# Audio_Amplifier.net
KiCad netlist of a schematic drawn in EAGLE
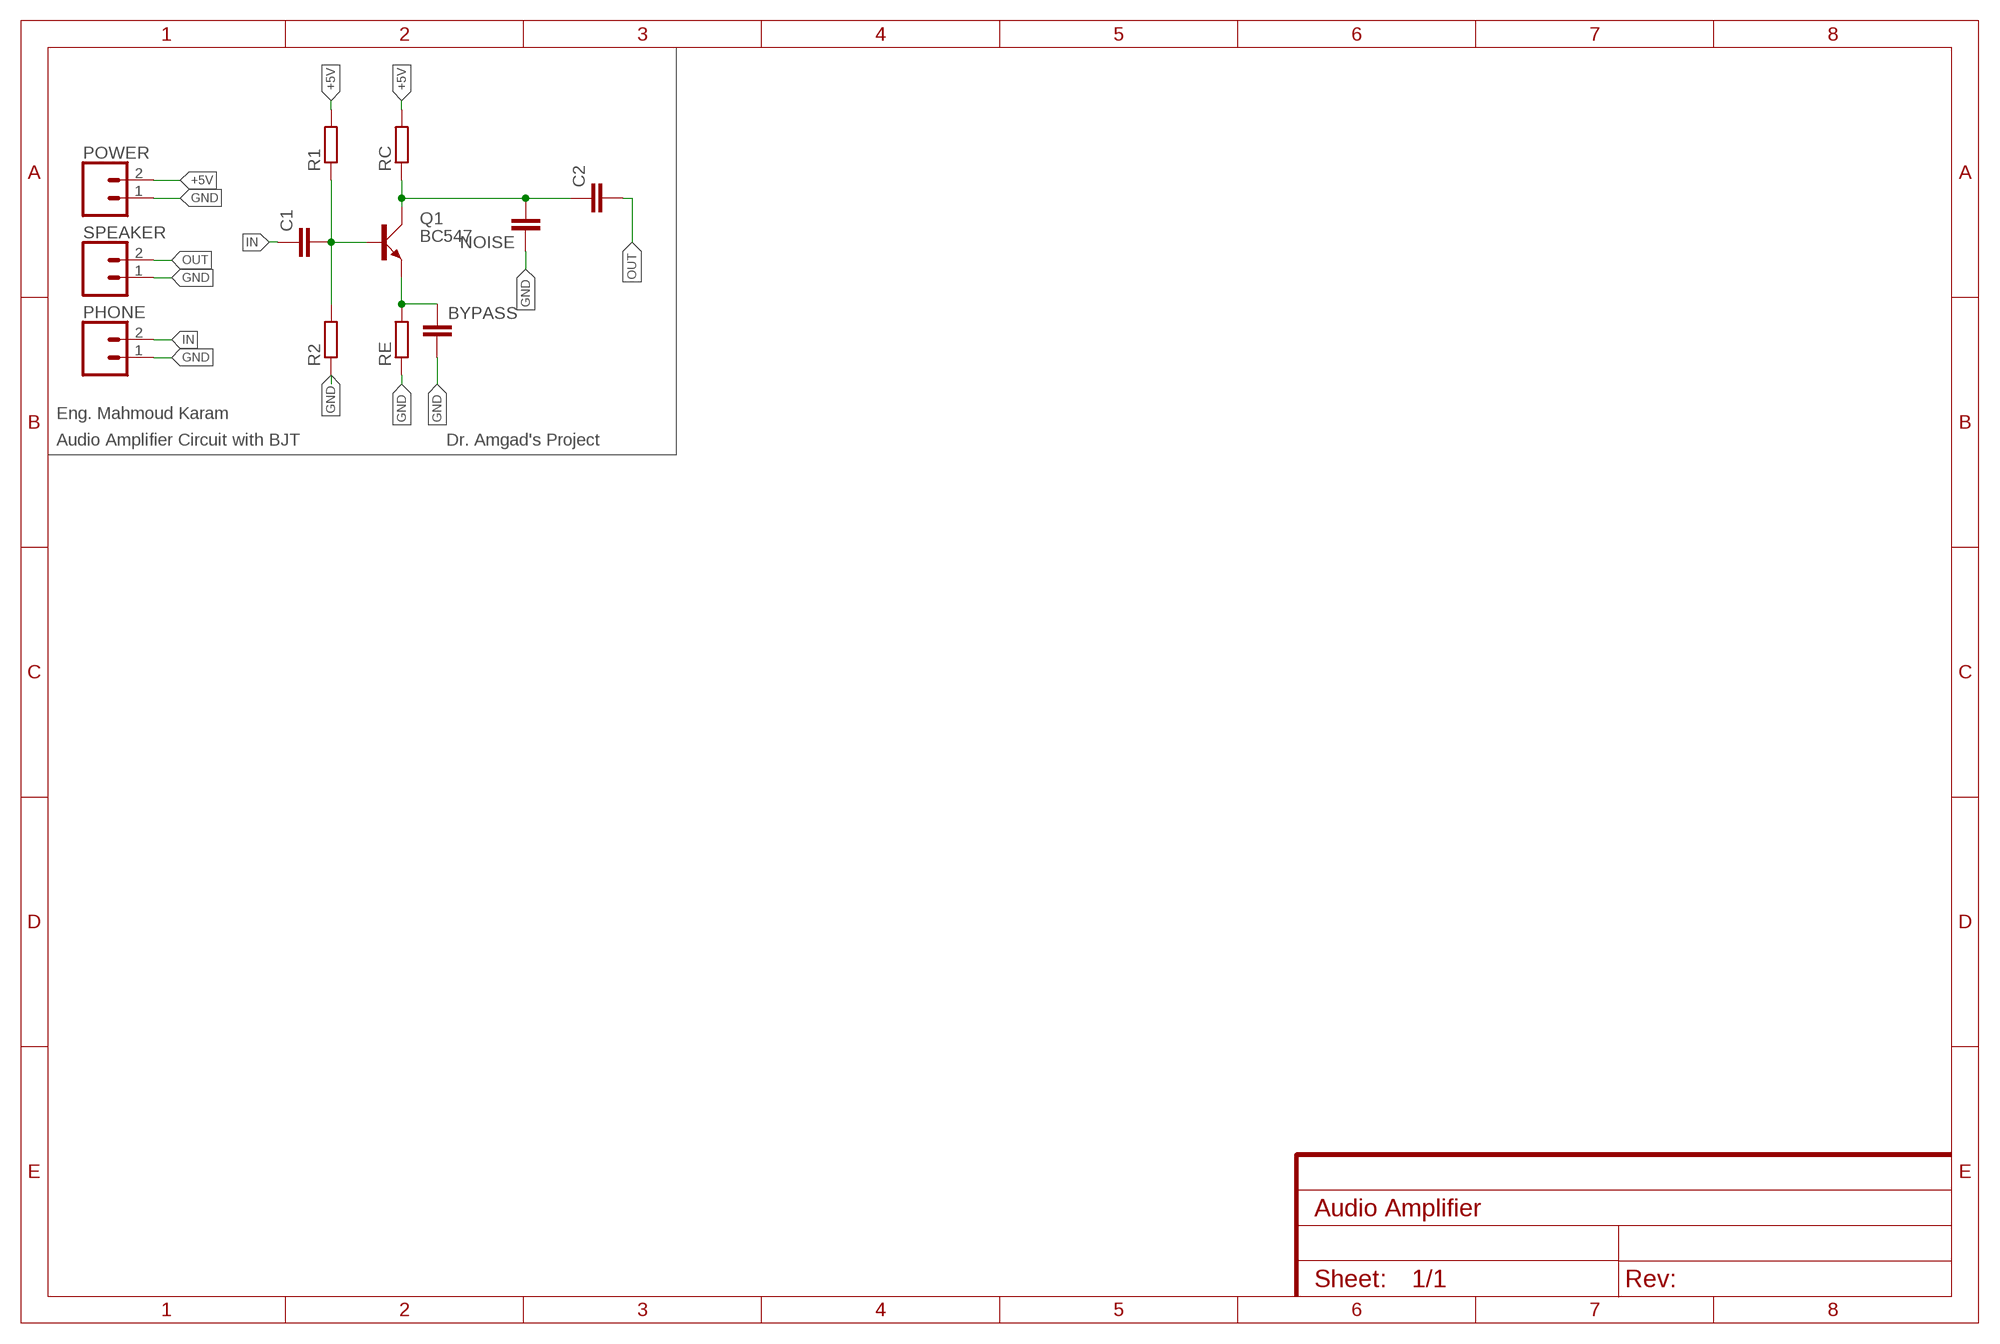
[diagram p0: schematic, sheet 1]

(export (version "E")
  (design (tool "Eeschema 10.0.6"))
  (components
    (comp (ref "BYPASS")
      (value "C10/4")
      (footprint "eagle-import:C10B4")
      (libsource (lib "eagle-import") (part "C10/4"))
    )
    (comp (ref "C1")
      (value "C2.5/5")
      (footprint "eagle-import:C2.5-5")
      (libsource (lib "eagle-import") (part "C2.5/5"))
    )
    (comp (ref "C2")
      (value "C2.5/5")
      (footprint "eagle-import:C2.5-5")
      (libsource (lib "eagle-import") (part "C2.5/5"))
    )
    (comp (ref "NOISE")
      (value "C2.5/5")
      (footprint "eagle-import:C2.5-5")
      (libsource (lib "eagle-import") (part "C2.5/5"))
    )
    (comp (ref "PHONE")
      (value "CONN_02JST-PTH-2")
      (footprint "eagle-import:JST-2-PTH")
      (libsource (lib "eagle-import") (part "CONN_02JST-PTH-2"))
    )
    (comp (ref "POWER")
      (value "CONN_02JST-PTH-2")
      (footprint "eagle-import:JST-2-PTH")
      (libsource (lib "eagle-import") (part "CONN_02JST-PTH-2"))
    )
    (comp (ref "Q1")
      (value "BC547")
      (footprint "eagle-import:SOT54A")
      (libsource (lib "eagle-import") (part "BC547"))
    )
    (comp (ref "R1")
      (value "R-EU_0204/7")
      (footprint "eagle-import:0204_7")
      (libsource (lib "eagle-import") (part "R-EU_0204/7"))
    )
    (comp (ref "R2")
      (value "R-EU_0204/7")
      (footprint "eagle-import:0204_7")
      (libsource (lib "eagle-import") (part "R-EU_0204/7"))
    )
    (comp (ref "RC")
      (value "R-EU_0204/7")
      (footprint "eagle-import:0204_7")
      (libsource (lib "eagle-import") (part "R-EU_0204/7"))
    )
    (comp (ref "RE")
      (value "R-EU_0204/7")
      (footprint "eagle-import:0204_7")
      (libsource (lib "eagle-import") (part "R-EU_0204/7"))
    )
    (comp (ref "SPEAKER")
      (value "CONN_02JST-PTH-2")
      (footprint "eagle-import:JST-2-PTH")
      (libsource (lib "eagle-import") (part "CONN_02JST-PTH-2"))
    )
  )
  (nets
    (net (code "1") (name "+5V") (class "Default")
      (node (ref "POWER") (pin "2") (pinfunction "2_2") (pintype "passive"))
      (node (ref "R1") (pin "2") (pinfunction "2_2") (pintype "passive"))
      (node (ref "RC") (pin "2") (pinfunction "2_2") (pintype "passive"))
    )
    (net (code "2") (name "GND") (class "Default")
      (node (ref "BYPASS") (pin "2") (pinfunction "2_2") (pintype "passive"))
      (node (ref "NOISE") (pin "1") (pinfunction "1_1") (pintype "passive"))
      (node (ref "PHONE") (pin "1") (pinfunction "1_1") (pintype "passive"))
      (node (ref "POWER") (pin "1") (pinfunction "1_1") (pintype "passive"))
      (node (ref "R2") (pin "1") (pinfunction "1_1") (pintype "passive"))
      (node (ref "RE") (pin "1") (pinfunction "1_1") (pintype "passive"))
      (node (ref "SPEAKER") (pin "1") (pinfunction "1_1") (pintype "passive"))
    )
    (net (code "3") (name "IN") (class "Default")
      (node (ref "C1") (pin "1") (pinfunction "1_1") (pintype "passive"))
      (node (ref "PHONE") (pin "2") (pinfunction "2_2") (pintype "passive"))
    )
    (net (code "4") (name "Net-(BYPASS-Pad1)") (class "Default")
      (node (ref "BYPASS") (pin "1") (pinfunction "1_1") (pintype "passive"))
      (node (ref "Q1") (pin "E") (pinfunction "E_E") (pintype "passive"))
      (node (ref "RE") (pin "2") (pinfunction "2_2") (pintype "passive"))
    )
    (net (code "5") (name "Net-(C1-Pad2)") (class "Default")
      (node (ref "C1") (pin "2") (pinfunction "2_2") (pintype "passive"))
      (node (ref "Q1") (pin "B") (pinfunction "B_B") (pintype "passive"))
      (node (ref "R1") (pin "1") (pinfunction "1_1") (pintype "passive"))
      (node (ref "R2") (pin "2") (pinfunction "2_2") (pintype "passive"))
    )
    (net (code "6") (name "Net-(C2-Pad1)") (class "Default")
      (node (ref "C2") (pin "1") (pinfunction "1_1") (pintype "passive"))
      (node (ref "NOISE") (pin "2") (pinfunction "2_2") (pintype "passive"))
      (node (ref "Q1") (pin "C") (pinfunction "C_C") (pintype "passive"))
      (node (ref "RC") (pin "1") (pinfunction "1_1") (pintype "passive"))
    )
    (net (code "7") (name "OUT") (class "Default")
      (node (ref "C2") (pin "2") (pinfunction "2_2") (pintype "passive"))
      (node (ref "SPEAKER") (pin "2") (pinfunction "2_2") (pintype "passive"))
    )
  )
)
